# M516X.net
KiCad netlist of a schematic drawn in EAGLE
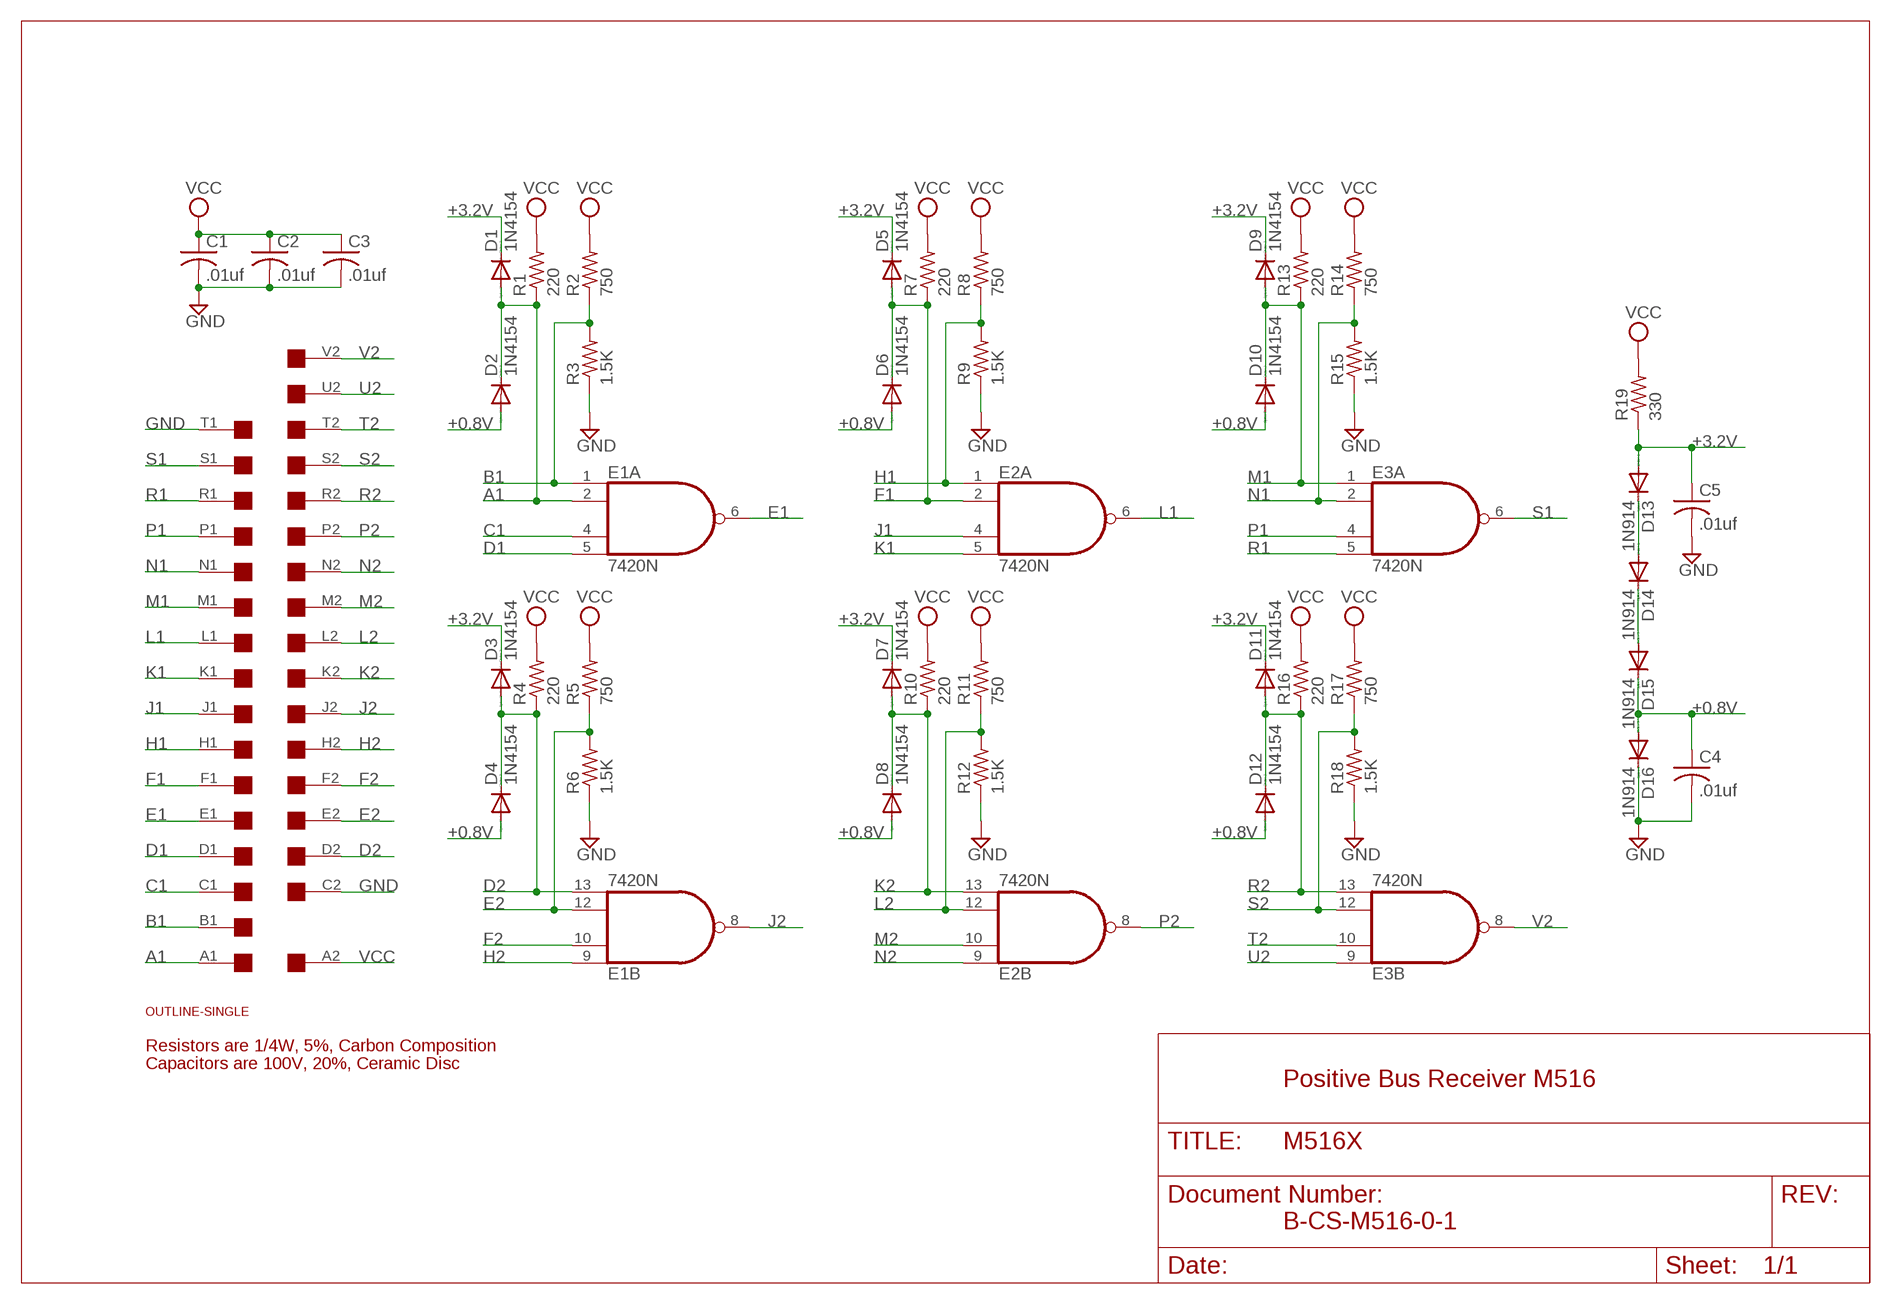
[diagram p0: schematic, sheet 1]

(export (version "E")
  (design (tool "Eeschema 10.0.6"))
  (components
    (comp (ref "C1")
      (value ".01uf")
      (footprint "eagle-import:C050-025X075")
      (libsource (lib "eagle-import") (part "C-US050-025X075"))
    )
    (comp (ref "C2")
      (value ".01uf")
      (footprint "eagle-import:C050-025X075")
      (libsource (lib "eagle-import") (part "C-US050-025X075"))
    )
    (comp (ref "C3")
      (value ".01uf")
      (footprint "eagle-import:C050-025X075")
      (libsource (lib "eagle-import") (part "C-US050-025X075"))
    )
    (comp (ref "C4")
      (value ".01uf")
      (footprint "eagle-import:C050-025X075")
      (libsource (lib "eagle-import") (part "C-US050-025X075"))
    )
    (comp (ref "C5")
      (value ".01uf")
      (footprint "eagle-import:C050-025X075")
      (libsource (lib "eagle-import") (part "C-US050-025X075"))
    )
    (comp (ref "D1")
      (value "1N4154")
      (footprint "eagle-import:DO35-10")
      (libsource (lib "eagle-import") (part "1N4148DO35-10"))
    )
    (comp (ref "D2")
      (value "1N4154")
      (footprint "eagle-import:DO35-10")
      (libsource (lib "eagle-import") (part "1N4148DO35-10"))
    )
    (comp (ref "D3")
      (value "1N4154")
      (footprint "eagle-import:DO35-10")
      (libsource (lib "eagle-import") (part "1N4148DO35-10"))
    )
    (comp (ref "D4")
      (value "1N4154")
      (footprint "eagle-import:DO35-10")
      (libsource (lib "eagle-import") (part "1N4148DO35-10"))
    )
    (comp (ref "D5")
      (value "1N4154")
      (footprint "eagle-import:DO35-10")
      (libsource (lib "eagle-import") (part "1N4148DO35-10"))
    )
    (comp (ref "D6")
      (value "1N4154")
      (footprint "eagle-import:DO35-10")
      (libsource (lib "eagle-import") (part "1N4148DO35-10"))
    )
    (comp (ref "D7")
      (value "1N4154")
      (footprint "eagle-import:DO35-10")
      (libsource (lib "eagle-import") (part "1N4148DO35-10"))
    )
    (comp (ref "D8")
      (value "1N4154")
      (footprint "eagle-import:DO35-10")
      (libsource (lib "eagle-import") (part "1N4148DO35-10"))
    )
    (comp (ref "D9")
      (value "1N4154")
      (footprint "eagle-import:DO35-10")
      (libsource (lib "eagle-import") (part "1N4148DO35-10"))
    )
    (comp (ref "D10")
      (value "1N4154")
      (footprint "eagle-import:DO35-10")
      (libsource (lib "eagle-import") (part "1N4148DO35-10"))
    )
    (comp (ref "D11")
      (value "1N4154")
      (footprint "eagle-import:DO35-10")
      (libsource (lib "eagle-import") (part "1N4148DO35-10"))
    )
    (comp (ref "D12")
      (value "1N4154")
      (footprint "eagle-import:DO35-10")
      (libsource (lib "eagle-import") (part "1N4148DO35-10"))
    )
    (comp (ref "D13")
      (value "1N914")
      (footprint "eagle-import:DO35-10")
      (libsource (lib "eagle-import") (part "1N4148DO35-10"))
    )
    (comp (ref "D14")
      (value "1N914")
      (footprint "eagle-import:DO35-10")
      (libsource (lib "eagle-import") (part "1N4148DO35-10"))
    )
    (comp (ref "D15")
      (value "1N914")
      (footprint "eagle-import:DO35-10")
      (libsource (lib "eagle-import") (part "1N4148DO35-10"))
    )
    (comp (ref "D16")
      (value "1N914")
      (footprint "eagle-import:DO35-10")
      (libsource (lib "eagle-import") (part "1N4148DO35-10"))
    )
    (comp (ref "E1")
      (value "7420N")
      (footprint "eagle-import:DIL14")
      (libsource (lib "eagle-import") (part "7420NS"))
    )
    (comp (ref "E2")
      (value "7420N")
      (footprint "eagle-import:DIL14")
      (libsource (lib "eagle-import") (part "7420NS"))
    )
    (comp (ref "E3")
      (value "7420N")
      (footprint "eagle-import:DIL14")
      (libsource (lib "eagle-import") (part "7420NS"))
    )
    (comp (ref "R1")
      (value "220")
      (footprint "eagle-import:0207_10")
      (libsource (lib "eagle-import") (part "R-US_0207/10"))
    )
    (comp (ref "R2")
      (value "750")
      (footprint "eagle-import:0207_10")
      (libsource (lib "eagle-import") (part "R-US_0207/10"))
    )
    (comp (ref "R3")
      (value "1.5K")
      (footprint "eagle-import:0207_10")
      (libsource (lib "eagle-import") (part "R-US_0207/10"))
    )
    (comp (ref "R4")
      (value "220")
      (footprint "eagle-import:0207_10")
      (libsource (lib "eagle-import") (part "R-US_0207/10"))
    )
    (comp (ref "R5")
      (value "750")
      (footprint "eagle-import:0207_10")
      (libsource (lib "eagle-import") (part "R-US_0207/10"))
    )
    (comp (ref "R6")
      (value "1.5K")
      (footprint "eagle-import:0207_10")
      (libsource (lib "eagle-import") (part "R-US_0207/10"))
    )
    (comp (ref "R7")
      (value "220")
      (footprint "eagle-import:0207_10")
      (libsource (lib "eagle-import") (part "R-US_0207/10"))
    )
    (comp (ref "R8")
      (value "750")
      (footprint "eagle-import:0207_10")
      (libsource (lib "eagle-import") (part "R-US_0207/10"))
    )
    (comp (ref "R9")
      (value "1.5K")
      (footprint "eagle-import:0207_10")
      (libsource (lib "eagle-import") (part "R-US_0207/10"))
    )
    (comp (ref "R10")
      (value "220")
      (footprint "eagle-import:0207_10")
      (libsource (lib "eagle-import") (part "R-US_0207/10"))
    )
    (comp (ref "R11")
      (value "750")
      (footprint "eagle-import:0207_10")
      (libsource (lib "eagle-import") (part "R-US_0207/10"))
    )
    (comp (ref "R12")
      (value "1.5K")
      (footprint "eagle-import:0207_10")
      (libsource (lib "eagle-import") (part "R-US_0207/10"))
    )
    (comp (ref "R13")
      (value "220")
      (footprint "eagle-import:0207_10")
      (libsource (lib "eagle-import") (part "R-US_0207/10"))
    )
    (comp (ref "R14")
      (value "750")
      (footprint "eagle-import:0207_10")
      (libsource (lib "eagle-import") (part "R-US_0207/10"))
    )
    (comp (ref "R15")
      (value "1.5K")
      (footprint "eagle-import:0207_10")
      (libsource (lib "eagle-import") (part "R-US_0207/10"))
    )
    (comp (ref "R16")
      (value "220")
      (footprint "eagle-import:0207_10")
      (libsource (lib "eagle-import") (part "R-US_0207/10"))
    )
    (comp (ref "R17")
      (value "750")
      (footprint "eagle-import:0207_10")
      (libsource (lib "eagle-import") (part "R-US_0207/10"))
    )
    (comp (ref "R18")
      (value "1.5K")
      (footprint "eagle-import:0207_10")
      (libsource (lib "eagle-import") (part "R-US_0207/10"))
    )
    (comp (ref "R19")
      (value "330")
      (footprint "eagle-import:0207_10")
      (libsource (lib "eagle-import") (part "R-US_0207/10"))
    )
    (comp (ref "U$1")
      (value "OUTLINE-SINGLE")
      (footprint "eagle-import:SINGLE")
      (libsource (lib "eagle-import") (part "OUTLINE-SINGLE"))
    )
    (comp (ref "U$2")
      (value "SINGLE")
      (footprint "eagle-import:EDGE-CON2")
      (libsource (lib "eagle-import") (part "SINGLE"))
    )
  )
  (nets
    (net (code "1") (name "/+0.8V") (class "Default")
      (node (ref "C4") (pin "1") (pinfunction "1_1") (pintype "passive"))
      (node (ref "D10") (pin "A") (pinfunction "A_A") (pintype "passive"))
      (node (ref "D12") (pin "A") (pinfunction "A_A") (pintype "passive"))
      (node (ref "D15") (pin "C") (pinfunction "C_C") (pintype "passive"))
      (node (ref "D16") (pin "A") (pinfunction "A_A") (pintype "passive"))
      (node (ref "D2") (pin "A") (pinfunction "A_A") (pintype "passive"))
      (node (ref "D4") (pin "A") (pinfunction "A_A") (pintype "passive"))
      (node (ref "D6") (pin "A") (pinfunction "A_A") (pintype "passive"))
      (node (ref "D8") (pin "A") (pinfunction "A_A") (pintype "passive"))
    )
    (net (code "2") (name "/+3.2V") (class "Default")
      (node (ref "C5") (pin "1") (pinfunction "1_1") (pintype "passive"))
      (node (ref "D1") (pin "C") (pinfunction "C_C") (pintype "passive"))
      (node (ref "D11") (pin "C") (pinfunction "C_C") (pintype "passive"))
      (node (ref "D13") (pin "A") (pinfunction "A_A") (pintype "passive"))
      (node (ref "D3") (pin "C") (pinfunction "C_C") (pintype "passive"))
      (node (ref "D5") (pin "C") (pinfunction "C_C") (pintype "passive"))
      (node (ref "D7") (pin "C") (pinfunction "C_C") (pintype "passive"))
      (node (ref "D9") (pin "C") (pinfunction "C_C") (pintype "passive"))
      (node (ref "R19") (pin "1") (pinfunction "1_1") (pintype "passive"))
    )
    (net (code "3") (name "/A1") (class "Default")
      (node (ref "D1") (pin "A") (pinfunction "A_A") (pintype "passive"))
      (node (ref "D2") (pin "C") (pinfunction "C_C") (pintype "passive"))
      (node (ref "E1") (pin "2") (pinfunction "I1_2") (pintype "input"))
      (node (ref "R1") (pin "1") (pinfunction "1_1") (pintype "passive"))
      (node (ref "U$2") (pin "A1") (pinfunction "1_A1") (pintype "bidirectional"))
    )
    (net (code "4") (name "/B1") (class "Default")
      (node (ref "E1") (pin "1") (pinfunction "I0_1") (pintype "input"))
      (node (ref "R2") (pin "1") (pinfunction "1_1") (pintype "passive"))
      (node (ref "R3") (pin "2") (pinfunction "2_2") (pintype "passive"))
      (node (ref "U$2") (pin "B1") (pinfunction "1_B1") (pintype "bidirectional"))
    )
    (net (code "5") (name "/C1") (class "Default")
      (node (ref "E1") (pin "4") (pinfunction "I2_4") (pintype "input"))
      (node (ref "U$2") (pin "C1") (pinfunction "1_C1") (pintype "bidirectional"))
    )
    (net (code "6") (name "/D1") (class "Default")
      (node (ref "E1") (pin "5") (pinfunction "I3_5") (pintype "input"))
      (node (ref "U$2") (pin "D1") (pinfunction "1_D1") (pintype "bidirectional"))
    )
    (net (code "7") (name "/D2") (class "Default")
      (node (ref "D3") (pin "A") (pinfunction "A_A") (pintype "passive"))
      (node (ref "D4") (pin "C") (pinfunction "C_C") (pintype "passive"))
      (node (ref "E1") (pin "13") (pinfunction "I3_13") (pintype "input"))
      (node (ref "R4") (pin "1") (pinfunction "1_1") (pintype "passive"))
      (node (ref "U$2") (pin "D2") (pinfunction "1_D2") (pintype "bidirectional"))
    )
    (net (code "8") (name "/E1") (class "Default")
      (node (ref "E1") (pin "6") (pinfunction "O_6") (pintype "output"))
      (node (ref "U$2") (pin "E1") (pinfunction "1_E1") (pintype "bidirectional"))
    )
    (net (code "9") (name "/E2") (class "Default")
      (node (ref "E1") (pin "12") (pinfunction "I2_12") (pintype "input"))
      (node (ref "R5") (pin "1") (pinfunction "1_1") (pintype "passive"))
      (node (ref "R6") (pin "2") (pinfunction "2_2") (pintype "passive"))
      (node (ref "U$2") (pin "E2") (pinfunction "1_E2") (pintype "bidirectional"))
    )
    (net (code "10") (name "/F1") (class "Default")
      (node (ref "D5") (pin "A") (pinfunction "A_A") (pintype "passive"))
      (node (ref "D6") (pin "C") (pinfunction "C_C") (pintype "passive"))
      (node (ref "E2") (pin "2") (pinfunction "I1_2") (pintype "input"))
      (node (ref "R7") (pin "1") (pinfunction "1_1") (pintype "passive"))
      (node (ref "U$2") (pin "F1") (pinfunction "1_F1") (pintype "bidirectional"))
    )
    (net (code "11") (name "/F2") (class "Default")
      (node (ref "E1") (pin "10") (pinfunction "I1_10") (pintype "input"))
      (node (ref "U$2") (pin "F2") (pinfunction "1_F2") (pintype "bidirectional"))
    )
    (net (code "12") (name "/H1") (class "Default")
      (node (ref "E2") (pin "1") (pinfunction "I0_1") (pintype "input"))
      (node (ref "R8") (pin "1") (pinfunction "1_1") (pintype "passive"))
      (node (ref "R9") (pin "2") (pinfunction "2_2") (pintype "passive"))
      (node (ref "U$2") (pin "H1") (pinfunction "1_H1") (pintype "bidirectional"))
    )
    (net (code "13") (name "/H2") (class "Default")
      (node (ref "E1") (pin "9") (pinfunction "I0_9") (pintype "input"))
      (node (ref "U$2") (pin "H2") (pinfunction "1_H2") (pintype "bidirectional"))
    )
    (net (code "14") (name "/J1") (class "Default")
      (node (ref "E2") (pin "4") (pinfunction "I2_4") (pintype "input"))
      (node (ref "U$2") (pin "J1") (pinfunction "1_J1") (pintype "bidirectional"))
    )
    (net (code "15") (name "/J2") (class "Default")
      (node (ref "E1") (pin "8") (pinfunction "O_8") (pintype "output"))
      (node (ref "U$2") (pin "J2") (pinfunction "1_J2") (pintype "bidirectional"))
    )
    (net (code "16") (name "/K1") (class "Default")
      (node (ref "E2") (pin "5") (pinfunction "I3_5") (pintype "input"))
      (node (ref "U$2") (pin "K1") (pinfunction "1_K1") (pintype "bidirectional"))
    )
    (net (code "17") (name "/K2") (class "Default")
      (node (ref "D7") (pin "A") (pinfunction "A_A") (pintype "passive"))
      (node (ref "D8") (pin "C") (pinfunction "C_C") (pintype "passive"))
      (node (ref "E2") (pin "13") (pinfunction "I3_13") (pintype "input"))
      (node (ref "R10") (pin "1") (pinfunction "1_1") (pintype "passive"))
      (node (ref "U$2") (pin "K2") (pinfunction "1_K2") (pintype "bidirectional"))
    )
    (net (code "18") (name "/L1") (class "Default")
      (node (ref "E2") (pin "6") (pinfunction "O_6") (pintype "output"))
      (node (ref "U$2") (pin "L1") (pinfunction "1_L1") (pintype "bidirectional"))
    )
    (net (code "19") (name "/L2") (class "Default")
      (node (ref "E2") (pin "12") (pinfunction "I2_12") (pintype "input"))
      (node (ref "R11") (pin "1") (pinfunction "1_1") (pintype "passive"))
      (node (ref "R12") (pin "2") (pinfunction "2_2") (pintype "passive"))
      (node (ref "U$2") (pin "L2") (pinfunction "1_L2") (pintype "bidirectional"))
    )
    (net (code "20") (name "/M1") (class "Default")
      (node (ref "D10") (pin "C") (pinfunction "C_C") (pintype "passive"))
      (node (ref "D9") (pin "A") (pinfunction "A_A") (pintype "passive"))
      (node (ref "E3") (pin "1") (pinfunction "I0_1") (pintype "input"))
      (node (ref "R13") (pin "1") (pinfunction "1_1") (pintype "passive"))
      (node (ref "U$2") (pin "M1") (pinfunction "1_M1") (pintype "bidirectional"))
    )
    (net (code "21") (name "/M2") (class "Default")
      (node (ref "E2") (pin "10") (pinfunction "I1_10") (pintype "input"))
      (node (ref "U$2") (pin "M2") (pinfunction "1_M2") (pintype "bidirectional"))
    )
    (net (code "22") (name "/N1") (class "Default")
      (node (ref "E3") (pin "2") (pinfunction "I1_2") (pintype "input"))
      (node (ref "R14") (pin "1") (pinfunction "1_1") (pintype "passive"))
      (node (ref "R15") (pin "2") (pinfunction "2_2") (pintype "passive"))
      (node (ref "U$2") (pin "N1") (pinfunction "1_N1") (pintype "bidirectional"))
    )
    (net (code "23") (name "/N2") (class "Default")
      (node (ref "E2") (pin "9") (pinfunction "I0_9") (pintype "input"))
      (node (ref "U$2") (pin "N2") (pinfunction "1_N2") (pintype "bidirectional"))
    )
    (net (code "24") (name "/P1") (class "Default")
      (node (ref "E3") (pin "4") (pinfunction "I2_4") (pintype "input"))
      (node (ref "U$2") (pin "P1") (pinfunction "1_P1") (pintype "bidirectional"))
    )
    (net (code "25") (name "/P2") (class "Default")
      (node (ref "E2") (pin "8") (pinfunction "O_8") (pintype "output"))
      (node (ref "U$2") (pin "P2") (pinfunction "1_P2") (pintype "bidirectional"))
    )
    (net (code "26") (name "/R1") (class "Default")
      (node (ref "E3") (pin "5") (pinfunction "I3_5") (pintype "input"))
      (node (ref "U$2") (pin "R1") (pinfunction "1_R1") (pintype "bidirectional"))
    )
    (net (code "27") (name "/R2") (class "Default")
      (node (ref "D11") (pin "A") (pinfunction "A_A") (pintype "passive"))
      (node (ref "D12") (pin "C") (pinfunction "C_C") (pintype "passive"))
      (node (ref "E3") (pin "13") (pinfunction "I3_13") (pintype "input"))
      (node (ref "R16") (pin "1") (pinfunction "1_1") (pintype "passive"))
      (node (ref "U$2") (pin "R2") (pinfunction "1_R2") (pintype "bidirectional"))
    )
    (net (code "28") (name "/S1") (class "Default")
      (node (ref "E3") (pin "6") (pinfunction "O_6") (pintype "output"))
      (node (ref "U$2") (pin "S1") (pinfunction "1_S1") (pintype "bidirectional"))
    )
    (net (code "29") (name "/S2") (class "Default")
      (node (ref "E3") (pin "12") (pinfunction "I2_12") (pintype "input"))
      (node (ref "R17") (pin "1") (pinfunction "1_1") (pintype "passive"))
      (node (ref "R18") (pin "2") (pinfunction "2_2") (pintype "passive"))
      (node (ref "U$2") (pin "S2") (pinfunction "1_S2") (pintype "bidirectional"))
    )
    (net (code "30") (name "/T2") (class "Default")
      (node (ref "E3") (pin "10") (pinfunction "I1_10") (pintype "input"))
      (node (ref "U$2") (pin "T2") (pinfunction "1_T2") (pintype "bidirectional"))
    )
    (net (code "31") (name "/U2") (class "Default")
      (node (ref "E3") (pin "9") (pinfunction "I0_9") (pintype "input"))
      (node (ref "U$2") (pin "U2") (pinfunction "1_U2") (pintype "bidirectional"))
    )
    (net (code "32") (name "/V2") (class "Default")
      (node (ref "E3") (pin "8") (pinfunction "O_8") (pintype "output"))
      (node (ref "U$2") (pin "V2") (pinfunction "1_V2") (pintype "bidirectional"))
    )
    (net (code "33") (name "GND") (class "Default")
      (node (ref "C1") (pin "2") (pinfunction "2_2") (pintype "passive"))
      (node (ref "C2") (pin "2") (pinfunction "2_2") (pintype "passive"))
      (node (ref "C3") (pin "2") (pinfunction "2_2") (pintype "passive"))
      (node (ref "C4") (pin "2") (pinfunction "2_2") (pintype "passive"))
      (node (ref "C5") (pin "2") (pinfunction "2_2") (pintype "passive"))
      (node (ref "D16") (pin "C") (pinfunction "C_C") (pintype "passive"))
      (node (ref "R12") (pin "1") (pinfunction "1_1") (pintype "passive"))
      (node (ref "R15") (pin "1") (pinfunction "1_1") (pintype "passive"))
      (node (ref "R18") (pin "1") (pinfunction "1_1") (pintype "passive"))
      (node (ref "R3") (pin "1") (pinfunction "1_1") (pintype "passive"))
      (node (ref "R6") (pin "1") (pinfunction "1_1") (pintype "passive"))
      (node (ref "R9") (pin "1") (pinfunction "1_1") (pintype "passive"))
      (node (ref "U$2") (pin "C2") (pinfunction "1_C2") (pintype "bidirectional"))
      (node (ref "U$2") (pin "T1") (pinfunction "1_T1") (pintype "bidirectional"))
    )
    (net (code "34") (name "Net-(D13-PadC)") (class "Default")
      (node (ref "D13") (pin "C") (pinfunction "C_C") (pintype "passive"))
      (node (ref "D14") (pin "A") (pinfunction "A_A") (pintype "passive"))
    )
    (net (code "35") (name "Net-(D14-PadC)") (class "Default")
      (node (ref "D14") (pin "C") (pinfunction "C_C") (pintype "passive"))
      (node (ref "D15") (pin "A") (pinfunction "A_A") (pintype "passive"))
    )
    (net (code "36") (name "VCC") (class "Default")
      (node (ref "C1") (pin "1") (pinfunction "1_1") (pintype "passive"))
      (node (ref "C2") (pin "1") (pinfunction "1_1") (pintype "passive"))
      (node (ref "C3") (pin "1") (pinfunction "1_1") (pintype "passive"))
      (node (ref "R1") (pin "2") (pinfunction "2_2") (pintype "passive"))
      (node (ref "R10") (pin "2") (pinfunction "2_2") (pintype "passive"))
      (node (ref "R11") (pin "2") (pinfunction "2_2") (pintype "passive"))
      (node (ref "R13") (pin "2") (pinfunction "2_2") (pintype "passive"))
      (node (ref "R14") (pin "2") (pinfunction "2_2") (pintype "passive"))
      (node (ref "R16") (pin "2") (pinfunction "2_2") (pintype "passive"))
      (node (ref "R17") (pin "2") (pinfunction "2_2") (pintype "passive"))
      (node (ref "R19") (pin "2") (pinfunction "2_2") (pintype "passive"))
      (node (ref "R2") (pin "2") (pinfunction "2_2") (pintype "passive"))
      (node (ref "R4") (pin "2") (pinfunction "2_2") (pintype "passive"))
      (node (ref "R5") (pin "2") (pinfunction "2_2") (pintype "passive"))
      (node (ref "R7") (pin "2") (pinfunction "2_2") (pintype "passive"))
      (node (ref "R8") (pin "2") (pinfunction "2_2") (pintype "passive"))
      (node (ref "U$2") (pin "A2") (pinfunction "1_A2") (pintype "bidirectional"))
    )
  )
)
